# sharp_esp32s2_v1.net
KiCad netlist of a schematic drawn in EAGLE
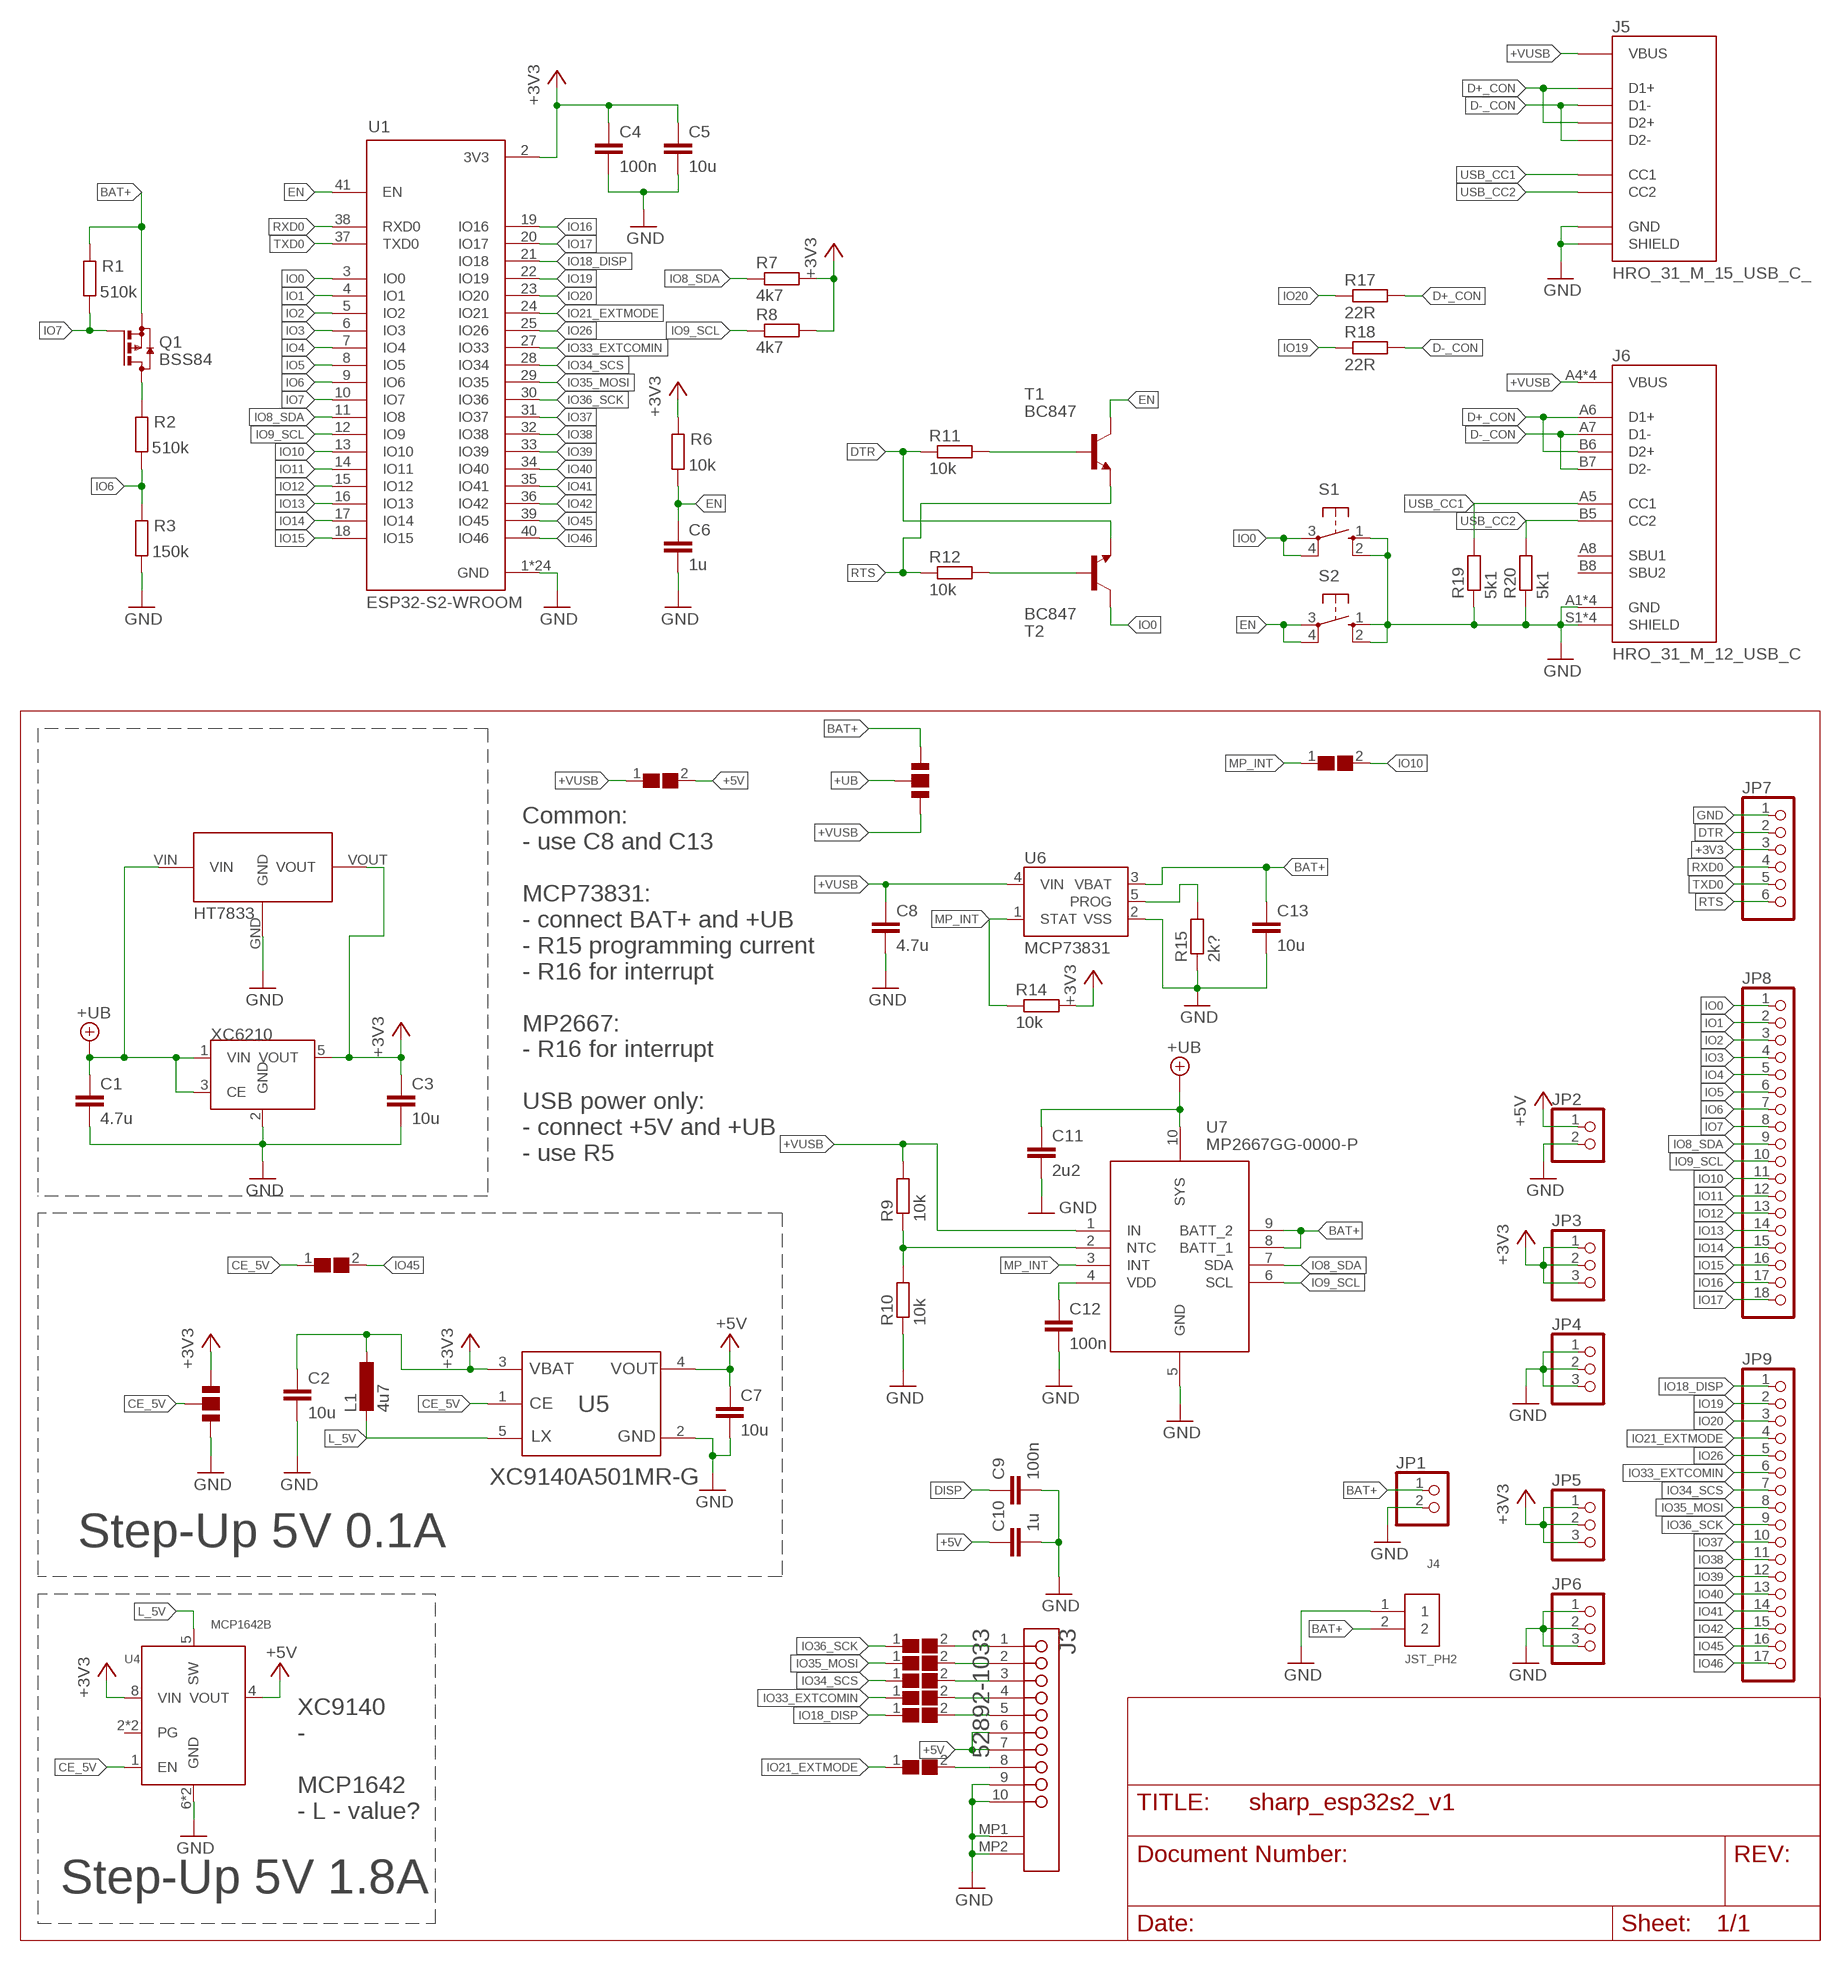
[diagram p0: schematic, sheet 1]

(export (version "E")
  (design (tool "Eeschema 10.0.6"))
  (components
    (comp (ref "C1")
      (value "4.7u")
      (footprint "eagle-import:C1206")
      (libsource (lib "eagle-import") (part "C-EUC1206"))
    )
    (comp (ref "C2")
      (value "10u")
      (footprint "eagle-import:C0603K")
      (libsource (lib "eagle-import") (part "C-EUC0603K"))
    )
    (comp (ref "C3")
      (value "10u")
      (footprint "eagle-import:C1206")
      (libsource (lib "eagle-import") (part "C-EUC1206"))
    )
    (comp (ref "C4")
      (value "100n")
      (footprint "eagle-import:C0603K")
      (libsource (lib "eagle-import") (part "C-EUC0603K"))
    )
    (comp (ref "C5")
      (value "10u")
      (footprint "eagle-import:C1206")
      (libsource (lib "eagle-import") (part "C-EUC1206"))
    )
    (comp (ref "C6")
      (value "1u")
      (footprint "eagle-import:C0603K")
      (libsource (lib "eagle-import") (part "C-EUC0603K"))
    )
    (comp (ref "C7")
      (value "10u")
      (footprint "eagle-import:C0603K")
      (libsource (lib "eagle-import") (part "C-EUC0603K"))
    )
    (comp (ref "C8")
      (value "4.7u")
      (footprint "eagle-import:C1206")
      (libsource (lib "eagle-import") (part "C-EUC1206"))
    )
    (comp (ref "C9")
      (value "100n")
      (footprint "eagle-import:C0603K")
      (libsource (lib "eagle-import") (part "C-EUC0603K"))
    )
    (comp (ref "C10")
      (value "1u")
      (footprint "eagle-import:C0603K")
      (libsource (lib "eagle-import") (part "C-EUC0603K"))
    )
    (comp (ref "C11")
      (value "2u2")
      (footprint "eagle-import:C1206")
      (libsource (lib "eagle-import") (part "C-EUC1206"))
    )
    (comp (ref "C12")
      (value "100n")
      (footprint "eagle-import:C0603K")
      (libsource (lib "eagle-import") (part "C-EUC0603K"))
    )
    (comp (ref "C13")
      (value "10u")
      (footprint "eagle-import:C1206")
      (libsource (lib "eagle-import") (part "C-EUC1206"))
    )
    (comp (ref "J1")
      (value "JUMPER")
      (footprint "eagle-import:2-WAY")
      (libsource (lib "eagle-import") (part "JUMPER"))
    )
    (comp (ref "J2")
      (value "JUMPER")
      (footprint "eagle-import:2-WAY")
      (libsource (lib "eagle-import") (part "JUMPER"))
    )
    (comp (ref "J3")
      (value "MOLEX_52892-1033MOLEX_52892-1033_0_0")
      (footprint "eagle-import:MOLEX_52892-1033_0")
      (fields (field (name "MF") "Molex") (field (name "MPN") "52892-1033"))
      (libsource (lib "eagle-import") (part "MOLEX_52892-1033MOLEX_52892-1033_0_0"))
    )
    (comp (ref "J4")
      (value "JST_PH2")
      (footprint "eagle-import:JSTPH2")
      (libsource (lib "eagle-import") (part "JST_PH2"))
    )
    (comp (ref "J5")
      (value "HRO_31_M_15_USB_C_")
      (footprint "eagle-import:HRO_31_M_15_USB_C")
      (libsource (lib "eagle-import") (part "HRO_31_M_15_USB_C_"))
    )
    (comp (ref "J6")
      (value "HRO_31_M_12_USB_C")
      (footprint "eagle-import:HRO_31_M_12_USB_C")
      (libsource (lib "eagle-import") (part "HRO_31_M_12_USB_C"))
    )
    (comp (ref "JP1")
      (value "PINHD-1X2")
      (footprint "eagle-import:1X02")
      (libsource (lib "eagle-import") (part "PINHD-1X2"))
    )
    (comp (ref "JP2")
      (value "PINHD-1X2")
      (footprint "eagle-import:1X02")
      (libsource (lib "eagle-import") (part "PINHD-1X2"))
    )
    (comp (ref "JP3")
      (value "PINHD-1X3")
      (footprint "eagle-import:1X03")
      (libsource (lib "eagle-import") (part "PINHD-1X3"))
    )
    (comp (ref "JP4")
      (value "PINHD-1X3")
      (footprint "eagle-import:1X03")
      (libsource (lib "eagle-import") (part "PINHD-1X3"))
    )
    (comp (ref "JP5")
      (value "PINHD-1X3")
      (footprint "eagle-import:1X03")
      (libsource (lib "eagle-import") (part "PINHD-1X3"))
    )
    (comp (ref "JP6")
      (value "PINHD-1X3")
      (footprint "eagle-import:1X03")
      (libsource (lib "eagle-import") (part "PINHD-1X3"))
    )
    (comp (ref "JP7")
      (value "PINHD-1X6")
      (footprint "eagle-import:1X06")
      (libsource (lib "eagle-import") (part "PINHD-1X6"))
    )
    (comp (ref "JP8")
      (value "PINHD-1X18")
      (footprint "eagle-import:1X18")
      (libsource (lib "eagle-import") (part "PINHD-1X18"))
    )
    (comp (ref "JP9")
      (value "PINHD-1X17")
      (footprint "eagle-import:1X17")
      (libsource (lib "eagle-import") (part "PINHD-1X17"))
    )
    (comp (ref "L1")
      (value "4u7")
      (footprint "eagle-import:L3225M")
      (libsource (lib "eagle-import") (part "L-EUL3225M"))
    )
    (comp (ref "Q1")
      (value "BSS84")
      (footprint "eagle-import:SOT23")
      (libsource (lib "eagle-import") (part "BSS84"))
    )
    (comp (ref "R1")
      (value "510k")
      (footprint "eagle-import:R0603")
      (libsource (lib "eagle-import") (part "R-EU_R0603"))
    )
    (comp (ref "R2")
      (value "510k")
      (footprint "eagle-import:R0603")
      (libsource (lib "eagle-import") (part "R-EU_R0603"))
    )
    (comp (ref "R3")
      (value "150k")
      (footprint "eagle-import:R0603")
      (libsource (lib "eagle-import") (part "R-EU_R0603"))
    )
    (comp (ref "R6")
      (value "10k")
      (footprint "eagle-import:R0603")
      (libsource (lib "eagle-import") (part "R-EU_R0603"))
    )
    (comp (ref "R7")
      (value "4k7")
      (footprint "eagle-import:R0603")
      (libsource (lib "eagle-import") (part "R-EU_R0603"))
    )
    (comp (ref "R8")
      (value "4k7")
      (footprint "eagle-import:R0603")
      (libsource (lib "eagle-import") (part "R-EU_R0603"))
    )
    (comp (ref "R9")
      (value "10k")
      (footprint "eagle-import:R0603")
      (libsource (lib "eagle-import") (part "R-EU_R0603"))
    )
    (comp (ref "R10")
      (value "10k")
      (footprint "eagle-import:R0603")
      (libsource (lib "eagle-import") (part "R-EU_R0603"))
    )
    (comp (ref "R11")
      (value "10k")
      (footprint "eagle-import:R0603")
      (libsource (lib "eagle-import") (part "R-EU_R0603"))
    )
    (comp (ref "R12")
      (value "10k")
      (footprint "eagle-import:R0603")
      (libsource (lib "eagle-import") (part "R-EU_R0603"))
    )
    (comp (ref "R14")
      (value "10k")
      (footprint "eagle-import:R0603")
      (libsource (lib "eagle-import") (part "R-EU_R0603"))
    )
    (comp (ref "R15")
      (value "2k?")
      (footprint "eagle-import:R0603")
      (libsource (lib "eagle-import") (part "R-EU_R0603"))
    )
    (comp (ref "R17")
      (value "22R")
      (footprint "eagle-import:R0603")
      (libsource (lib "eagle-import") (part "R-EU_R0603"))
    )
    (comp (ref "R18")
      (value "22R")
      (footprint "eagle-import:R0603")
      (libsource (lib "eagle-import") (part "R-EU_R0603"))
    )
    (comp (ref "R19")
      (value "5k1")
      (footprint "eagle-import:R0603")
      (libsource (lib "eagle-import") (part "R-EU_R0603"))
    )
    (comp (ref "R20")
      (value "5k1")
      (footprint "eagle-import:R0603")
      (libsource (lib "eagle-import") (part "R-EU_R0603"))
    )
    (comp (ref "S1")
      (value "10-XX")
      (footprint "eagle-import:B3F-10XX")
      (fields (field (name "MPN") "B3F-1000"))
      (libsource (lib "eagle-import") (part "10-XX"))
    )
    (comp (ref "S2")
      (value "10-XX")
      (footprint "eagle-import:B3F-10XX")
      (fields (field (name "MPN") "B3F-1000"))
      (libsource (lib "eagle-import") (part "10-XX"))
    )
    (comp (ref "T1")
      (value "BC847")
      (footprint "eagle-import:SOT23")
      (libsource (lib "eagle-import") (part "BC847"))
    )
    (comp (ref "T2")
      (value "BC847")
      (footprint "eagle-import:SOT23")
      (libsource (lib "eagle-import") (part "BC847"))
    )
    (comp (ref "U$1")
      (value "SOLDER_JUMPER")
      (footprint "eagle-import:SOLDER_JUMPER")
      (libsource (lib "eagle-import") (part "SOLDER_JUMPER"))
    )
    (comp (ref "U$2")
      (value "SOLDER_JUMPER")
      (footprint "eagle-import:SOLDER_JUMPER")
      (libsource (lib "eagle-import") (part "SOLDER_JUMPER"))
    )
    (comp (ref "U$3")
      (value "SOLDER_JUMPER")
      (footprint "eagle-import:SOLDER_JUMPER")
      (libsource (lib "eagle-import") (part "SOLDER_JUMPER"))
    )
    (comp (ref "U$4")
      (value "SOLDER_JUMPER")
      (footprint "eagle-import:SOLDER_JUMPER")
      (libsource (lib "eagle-import") (part "SOLDER_JUMPER"))
    )
    (comp (ref "U$5")
      (value "SOLDER_JUMPER")
      (footprint "eagle-import:SOLDER_JUMPER")
      (libsource (lib "eagle-import") (part "SOLDER_JUMPER"))
    )
    (comp (ref "U$6")
      (value "SOLDER_JUMPER")
      (footprint "eagle-import:SOLDER_JUMPER")
      (libsource (lib "eagle-import") (part "SOLDER_JUMPER"))
    )
    (comp (ref "U$7")
      (value "SOLDER_JUMPER")
      (footprint "eagle-import:SOLDER_JUMPER")
      (libsource (lib "eagle-import") (part "SOLDER_JUMPER"))
    )
    (comp (ref "U$8")
      (value "SOLDER_JUMPER")
      (footprint "eagle-import:SOLDER_JUMPER")
      (libsource (lib "eagle-import") (part "SOLDER_JUMPER"))
    )
    (comp (ref "U$9")
      (value "SOLDER_JUMPER")
      (footprint "eagle-import:SOLDER_JUMPER")
      (libsource (lib "eagle-import") (part "SOLDER_JUMPER"))
    )
    (comp (ref "U1")
      (value "ESP32-S2-WROOM")
      (footprint "eagle-import:XCVR_ESP32-S2-WROOM")
      (fields (field (name "MF") "Espressif Systems"))
      (libsource (lib "eagle-import") (part "ESP32-S2-WROOM"))
    )
    (comp (ref "U2")
      (value "HT7833")
      (footprint "eagle-import:SOT89")
      (libsource (lib "eagle-import") (part "HT7833"))
    )
    (comp (ref "U3")
      (value "XC6210")
      (footprint "eagle-import:SOT-23-5")
      (libsource (lib "eagle-import") (part "XC6210"))
    )
    (comp (ref "U4")
      (value "MCP1642B")
      (footprint "eagle-import:MSOP8")
      (libsource (lib "eagle-import") (part "MCP1642B"))
    )
    (comp (ref "U5")
      (value "TOREX_XC9140A501MR-GTOREX_XC9140A501MR-G_0_0")
      (footprint "eagle-import:TOREX_XC9140A501MR-G_0")
      (fields
        (field (name "DIGIKEY_PART_NUMBER") "893-1181-1-ND")
        (field (name "MF") "Torex")
        (field (name "MOUSER_PART_NUMBER") "865-XC9140A501MR-G")
      )
      (libsource (lib "eagle-import") (part "TOREX_XC9140A501MR-GTOREX_XC9140A501MR-G_0_0"))
    )
    (comp (ref "U6")
      (value "MCP73831")
      (footprint "eagle-import:SOT95P290X120-5")
      (libsource (lib "eagle-import") (part "MCP73831"))
    )
    (comp (ref "U7")
      (value "MP2667GG-0000-P")
      (footprint "eagle-import:QFN50P200X200X105-10N")
      (fields (field (name "MOUSER_PART_NUMBER") "946-MP2667GG-0000-P"))
      (libsource (lib "eagle-import") (part "MP2667GG-0000-P"))
    )
  )
  (nets
    (net (code "1") (name "+3V3") (class "Default")
      (node (ref "C2") (pin "1") (pinfunction "1_1") (pintype "passive"))
      (node (ref "C3") (pin "1") (pinfunction "1_1") (pintype "passive"))
      (node (ref "C4") (pin "1") (pinfunction "1_1") (pintype "passive"))
      (node (ref "C5") (pin "1") (pinfunction "1_1") (pintype "passive"))
      (node (ref "J1") (pin "P$3") (pinfunction "P$3_P$3") (pintype "bidirectional"))
      (node (ref "JP3") (pin "1") (pinfunction "1_1") (pintype "passive"))
      (node (ref "JP3") (pin "2") (pinfunction "2_2") (pintype "passive"))
      (node (ref "JP3") (pin "3") (pinfunction "3_3") (pintype "passive"))
      (node (ref "JP5") (pin "1") (pinfunction "1_1") (pintype "passive"))
      (node (ref "JP5") (pin "2") (pinfunction "2_2") (pintype "passive"))
      (node (ref "JP5") (pin "3") (pinfunction "3_3") (pintype "passive"))
      (node (ref "JP7") (pin "3") (pinfunction "3_3") (pintype "passive"))
      (node (ref "L1") (pin "1") (pinfunction "1_1") (pintype "passive"))
      (node (ref "R14") (pin "2") (pinfunction "2_2") (pintype "passive"))
      (node (ref "R6") (pin "2") (pinfunction "2_2") (pintype "passive"))
      (node (ref "R7") (pin "2") (pinfunction "2_2") (pintype "passive"))
      (node (ref "R8") (pin "2") (pinfunction "2_2") (pintype "passive"))
      (node (ref "U1") (pin "2") (pinfunction "3V3_2") (pintype "power_in"))
      (node (ref "U2") (pin "VOUT") (pinfunction "VOUT_VOUT") (pintype "bidirectional"))
      (node (ref "U3") (pin "5") (pinfunction "VOUT_5") (pintype "power_in"))
      (node (ref "U4") (pin "8") (pinfunction "VIN_8") (pintype "power_in"))
      (node (ref "U5") (pin "3") (pinfunction "VBAT_3") (pintype "input"))
    )
    (net (code "2") (name "+5V") (class "Default")
      (node (ref "C10") (pin "1") (pinfunction "1_1") (pintype "passive"))
      (node (ref "C7") (pin "1") (pinfunction "1_1") (pintype "passive"))
      (node (ref "J3") (pin "6") (pinfunction "6_6") (pintype "passive"))
      (node (ref "J3") (pin "7") (pinfunction "7_7") (pintype "passive"))
      (node (ref "JP2") (pin "1") (pinfunction "1_1") (pintype "passive"))
      (node (ref "U$7") (pin "2") (pinfunction "2_2") (pintype "bidirectional"))
      (node (ref "U4") (pin "4") (pinfunction "VOUT_4") (pintype "power_in"))
      (node (ref "U5") (pin "4") (pinfunction "VOUT_4") (pintype "output"))
    )
    (net (code "3") (name "+UB") (class "Default")
      (node (ref "C1") (pin "1") (pinfunction "1_1") (pintype "passive"))
      (node (ref "C11") (pin "1") (pinfunction "1_1") (pintype "passive"))
      (node (ref "J2") (pin "P$1") (pinfunction "P$1_P$1") (pintype "bidirectional"))
      (node (ref "U2") (pin "VIN") (pinfunction "VIN_VIN") (pintype "bidirectional"))
      (node (ref "U3") (pin "1") (pinfunction "VIN_1") (pintype "power_in"))
      (node (ref "U3") (pin "3") (pinfunction "CE_3") (pintype "power_in"))
      (node (ref "U7") (pin "10") (pinfunction "SYS_10") (pintype "bidirectional"))
    )
    (net (code "4") (name "+VUSB") (class "Default")
      (node (ref "C8") (pin "1") (pinfunction "1_1") (pintype "passive"))
      (node (ref "J2") (pin "P$2") (pinfunction "P$2_P$2") (pintype "bidirectional"))
      (node (ref "J5") (pin "P$13") (pinfunction "VBUS_P$13") (pintype "passive"))
      (node (ref "J5") (pin "P$2") (pinfunction "VBUS_P$2") (pintype "passive"))
      (node (ref "J5") (pin "P$6") (pinfunction "VBUS_P$6") (pintype "passive"))
      (node (ref "J5") (pin "P$9") (pinfunction "VBUS_P$9") (pintype "passive"))
      (node (ref "J6") (pin "A4") (pinfunction "VBUS_A4") (pintype "passive"))
      (node (ref "J6") (pin "A9") (pinfunction "VBUS_A9") (pintype "passive"))
      (node (ref "J6") (pin "B4") (pinfunction "VBUS_B4") (pintype "passive"))
      (node (ref "J6") (pin "B9") (pinfunction "VBUS_B9") (pintype "passive"))
      (node (ref "R9") (pin "2") (pinfunction "2_2") (pintype "passive"))
      (node (ref "U$7") (pin "1") (pinfunction "1_1") (pintype "bidirectional"))
      (node (ref "U6") (pin "4") (pinfunction "VIN_4") (pintype "power_in"))
      (node (ref "U7") (pin "1") (pinfunction "IN_1") (pintype "bidirectional"))
    )
    (net (code "5") (name "BAT+") (class "Default")
      (node (ref "C13") (pin "1") (pinfunction "1_1") (pintype "passive"))
      (node (ref "J2") (pin "P$3") (pinfunction "P$3_P$3") (pintype "bidirectional"))
      (node (ref "J4") (pin "2") (pinfunction "2_2") (pintype "bidirectional"))
      (node (ref "JP1") (pin "1") (pinfunction "1_1") (pintype "passive"))
      (node (ref "Q1") (pin "2") (pinfunction "S_2") (pintype "passive"))
      (node (ref "R1") (pin "2") (pinfunction "2_2") (pintype "passive"))
      (node (ref "U6") (pin "3") (pinfunction "VBAT_3") (pintype "power_in"))
      (node (ref "U7") (pin "8") (pinfunction "BATT_1_8") (pintype "bidirectional"))
      (node (ref "U7") (pin "9") (pinfunction "BATT_2_9") (pintype "bidirectional"))
    )
    (net (code "6") (name "CE_5V") (class "Default")
      (node (ref "J1") (pin "P$1") (pinfunction "P$1_P$1") (pintype "bidirectional"))
      (node (ref "U$9") (pin "1") (pinfunction "1_1") (pintype "bidirectional"))
      (node (ref "U4") (pin "1") (pinfunction "EN_1") (pintype "input"))
      (node (ref "U5") (pin "1") (pinfunction "CE_1") (pintype "passive"))
    )
    (net (code "7") (name "D+_CON") (class "Default")
      (node (ref "J5") (pin "P$11") (pinfunction "D2+_P$11") (pintype "passive"))
      (node (ref "J5") (pin "P$4") (pinfunction "D1+_P$4") (pintype "passive"))
      (node (ref "J6") (pin "A6") (pinfunction "D1+_A6") (pintype "passive"))
      (node (ref "J6") (pin "B6") (pinfunction "D2+_B6") (pintype "passive"))
      (node (ref "R17") (pin "2") (pinfunction "2_2") (pintype "passive"))
    )
    (net (code "8") (name "D-_CON") (class "Default")
      (node (ref "J5") (pin "P$10") (pinfunction "D2-_P$10") (pintype "passive"))
      (node (ref "J5") (pin "P$3") (pinfunction "D1-_P$3") (pintype "passive"))
      (node (ref "J6") (pin "A7") (pinfunction "D1-_A7") (pintype "passive"))
      (node (ref "J6") (pin "B7") (pinfunction "D2-_B7") (pintype "passive"))
      (node (ref "R18") (pin "2") (pinfunction "2_2") (pintype "passive"))
    )
    (net (code "9") (name "DISP") (class "Default")
      (node (ref "C9") (pin "1") (pinfunction "1_1") (pintype "passive"))
      (node (ref "J3") (pin "5") (pinfunction "5_5") (pintype "passive"))
      (node (ref "U$5") (pin "2") (pinfunction "2_2") (pintype "bidirectional"))
    )
    (net (code "10") (name "DTR") (class "Default")
      (node (ref "JP7") (pin "2") (pinfunction "2_2") (pintype "passive"))
      (node (ref "R11") (pin "1") (pinfunction "1_1") (pintype "passive"))
      (node (ref "T2") (pin "2") (pinfunction "E_2") (pintype "passive"))
    )
    (net (code "11") (name "EN") (class "Default")
      (node (ref "C6") (pin "1") (pinfunction "1_1") (pintype "passive"))
      (node (ref "R6") (pin "1") (pinfunction "1_1") (pintype "passive"))
      (node (ref "S2") (pin "3") (pinfunction "P_3") (pintype "passive"))
      (node (ref "S2") (pin "4") (pinfunction "P1_4") (pintype "passive"))
      (node (ref "T1") (pin "3") (pinfunction "C_3") (pintype "passive"))
      (node (ref "U1") (pin "41") (pinfunction "EN_41") (pintype "input"))
    )
    (net (code "12") (name "GND") (class "Default")
      (node (ref "C1") (pin "2") (pinfunction "2_2") (pintype "passive"))
      (node (ref "C10") (pin "2") (pinfunction "2_2") (pintype "passive"))
      (node (ref "C11") (pin "2") (pinfunction "2_2") (pintype "passive"))
      (node (ref "C12") (pin "2") (pinfunction "2_2") (pintype "passive"))
      (node (ref "C13") (pin "2") (pinfunction "2_2") (pintype "passive"))
      (node (ref "C2") (pin "2") (pinfunction "2_2") (pintype "passive"))
      (node (ref "C3") (pin "2") (pinfunction "2_2") (pintype "passive"))
      (node (ref "C4") (pin "2") (pinfunction "2_2") (pintype "passive"))
      (node (ref "C5") (pin "2") (pinfunction "2_2") (pintype "passive"))
      (node (ref "C6") (pin "2") (pinfunction "2_2") (pintype "passive"))
      (node (ref "C7") (pin "2") (pinfunction "2_2") (pintype "passive"))
      (node (ref "C8") (pin "2") (pinfunction "2_2") (pintype "passive"))
      (node (ref "C9") (pin "2") (pinfunction "2_2") (pintype "passive"))
      (node (ref "J1") (pin "P$2") (pinfunction "P$2_P$2") (pintype "bidirectional"))
      (node (ref "J3") (pin "10") (pinfunction "10_10") (pintype "passive"))
      (node (ref "J3") (pin "9") (pinfunction "9_9") (pintype "passive"))
      (node (ref "J3") (pin "MP1") (pinfunction "MP1_MP1") (pintype "passive"))
      (node (ref "J3") (pin "MP2") (pinfunction "MP2_MP2") (pintype "passive"))
      (node (ref "J4") (pin "1") (pinfunction "1_1") (pintype "bidirectional"))
      (node (ref "J5") (pin "P$1") (pinfunction "GND_P$1") (pintype "passive"))
      (node (ref "J5") (pin "P$14") (pinfunction "GND_P$14") (pintype "passive"))
      (node (ref "J5") (pin "P$15") (pinfunction "SHIELD_P$15") (pintype "passive"))
      (node (ref "J5") (pin "P$16") (pinfunction "SHIELD_P$16") (pintype "passive"))
      (node (ref "J5") (pin "P$17") (pinfunction "SHIELD_P$17") (pintype "passive"))
      (node (ref "J5") (pin "P$18") (pinfunction "SHIELD_P$18") (pintype "passive"))
      (node (ref "J5") (pin "P$7") (pinfunction "GND_P$7") (pintype "passive"))
      (node (ref "J5") (pin "P$8") (pinfunction "GND_P$8") (pintype "passive"))
      (node (ref "J6") (pin "A1") (pinfunction "GND_A1") (pintype "passive"))
      (node (ref "J6") (pin "A12") (pinfunction "GND_A12") (pintype "passive"))
      (node (ref "J6") (pin "B1") (pinfunction "GND_B1") (pintype "passive"))
      (node (ref "J6") (pin "B12") (pinfunction "GND_B12") (pintype "passive"))
      (node (ref "J6") (pin "S1") (pinfunction "SHIELD_S1") (pintype "passive"))
      (node (ref "J6") (pin "S2") (pinfunction "SHIELD_S2") (pintype "passive"))
      (node (ref "J6") (pin "S3") (pinfunction "SHIELD_S3") (pintype "passive"))
      (node (ref "J6") (pin "S4") (pinfunction "SHIELD_S4") (pintype "passive"))
      (node (ref "JP1") (pin "2") (pinfunction "2_2") (pintype "passive"))
      (node (ref "JP2") (pin "2") (pinfunction "2_2") (pintype "passive"))
      (node (ref "JP4") (pin "1") (pinfunction "1_1") (pintype "passive"))
      (node (ref "JP4") (pin "2") (pinfunction "2_2") (pintype "passive"))
      (node (ref "JP4") (pin "3") (pinfunction "3_3") (pintype "passive"))
      (node (ref "JP6") (pin "1") (pinfunction "1_1") (pintype "passive"))
      (node (ref "JP6") (pin "2") (pinfunction "2_2") (pintype "passive"))
      (node (ref "JP6") (pin "3") (pinfunction "3_3") (pintype "passive"))
      (node (ref "JP7") (pin "1") (pinfunction "1_1") (pintype "passive"))
      (node (ref "R10") (pin "1") (pinfunction "1_1") (pintype "passive"))
      (node (ref "R15") (pin "1") (pinfunction "1_1") (pintype "passive"))
      (node (ref "R19") (pin "1") (pinfunction "1_1") (pintype "passive"))
      (node (ref "R20") (pin "1") (pinfunction "1_1") (pintype "passive"))
      (node (ref "R3") (pin "1") (pinfunction "1_1") (pintype "passive"))
      (node (ref "S1") (pin "1") (pinfunction "S_1") (pintype "passive"))
      (node (ref "S1") (pin "2") (pinfunction "S1_2") (pintype "passive"))
      (node (ref "S2") (pin "1") (pinfunction "S_1") (pintype "passive"))
      (node (ref "S2") (pin "2") (pinfunction "S1_2") (pintype "passive"))
      (node (ref "U1") (pin "1") (pinfunction "GND_1") (pintype "power_in"))
      (node (ref "U1") (pin "26") (pinfunction "GND_26") (pintype "power_in"))
      (node (ref "U1") (pin "42") (pinfunction "GND_42") (pintype "power_in"))
      (node (ref "U1") (pin "43.1") (pinfunction "GND_43.1") (pintype "power_in"))
      (node (ref "U1") (pin "43.10") (pinfunction "GND_43.10") (pintype "power_in"))
      (node (ref "U1") (pin "43.11") (pinfunction "GND_43.11") (pintype "power_in"))
      (node (ref "U1") (pin "43.12") (pinfunction "GND_43.12") (pintype "power_in"))
      (node (ref "U1") (pin "43.13") (pinfunction "GND_43.13") (pintype "power_in"))
      (node (ref "U1") (pin "43.14") (pinfunction "GND_43.14") (pintype "power_in"))
      (node (ref "U1") (pin "43.15") (pinfunction "GND_43.15") (pintype "power_in"))
      (node (ref "U1") (pin "43.16") (pinfunction "GND_43.16") (pintype "power_in"))
      (node (ref "U1") (pin "43.17") (pinfunction "GND_43.17") (pintype "power_in"))
      (node (ref "U1") (pin "43.18") (pinfunction "GND_43.18") (pintype "power_in"))
      (node (ref "U1") (pin "43.19") (pinfunction "GND_43.19") (pintype "power_in"))
      (node (ref "U1") (pin "43.2") (pinfunction "GND_43.2") (pintype "power_in"))
      (node (ref "U1") (pin "43.20") (pinfunction "GND_43.20") (pintype "power_in"))
      (node (ref "U1") (pin "43.21") (pinfunction "GND_43.21") (pintype "power_in"))
      (node (ref "U1") (pin "43.3") (pinfunction "GND_43.3") (pintype "power_in"))
      (node (ref "U1") (pin "43.4") (pinfunction "GND_43.4") (pintype "power_in"))
      (node (ref "U1") (pin "43.5") (pinfunction "GND_43.5") (pintype "power_in"))
      (node (ref "U1") (pin "43.6") (pinfunction "GND_43.6") (pintype "power_in"))
      (node (ref "U1") (pin "43.7") (pinfunction "GND_43.7") (pintype "power_in"))
      (node (ref "U1") (pin "43.8") (pinfunction "GND_43.8") (pintype "power_in"))
      (node (ref "U1") (pin "43.9") (pinfunction "GND_43.9") (pintype "power_in"))
      (node (ref "U2") (pin "GND") (pinfunction "GND_GND") (pintype "bidirectional"))
      (node (ref "U3") (pin "2") (pinfunction "GND_2") (pintype "power_in"))
      (node (ref "U4") (pin "6") (pinfunction "GND_6") (pintype "power_in"))
      (node (ref "U4") (pin "7") (pinfunction "GND_7") (pintype "power_in"))
      (node (ref "U5") (pin "2") (pinfunction "GND_2") (pintype "power_in"))
      (node (ref "U6") (pin "2") (pinfunction "VSS_2") (pintype "power_in"))
      (node (ref "U7") (pin "5") (pinfunction "GND_5") (pintype "bidirectional"))
    )
    (net (code "13") (name "IO0") (class "Default")
      (node (ref "JP8") (pin "1") (pinfunction "1_1") (pintype "passive"))
      (node (ref "S1") (pin "3") (pinfunction "P_3") (pintype "passive"))
      (node (ref "S1") (pin "4") (pinfunction "P1_4") (pintype "passive"))
      (node (ref "T2") (pin "3") (pinfunction "C_3") (pintype "passive"))
      (node (ref "U1") (pin "3") (pinfunction "IO0_3") (pintype "bidirectional"))
    )
    (net (code "14") (name "IO1") (class "Default")
      (node (ref "JP8") (pin "2") (pinfunction "2_2") (pintype "passive"))
      (node (ref "U1") (pin "4") (pinfunction "IO1_4") (pintype "bidirectional"))
    )
    (net (code "15") (name "IO2") (class "Default")
      (node (ref "JP8") (pin "3") (pinfunction "3_3") (pintype "passive"))
      (node (ref "U1") (pin "5") (pinfunction "IO2_5") (pintype "bidirectional"))
    )
    (net (code "16") (name "IO3") (class "Default")
      (node (ref "JP8") (pin "4") (pinfunction "4_4") (pintype "passive"))
      (node (ref "U1") (pin "6") (pinfunction "IO3_6") (pintype "bidirectional"))
    )
    (net (code "17") (name "IO4") (class "Default")
      (node (ref "JP8") (pin "5") (pinfunction "5_5") (pintype "passive"))
      (node (ref "U1") (pin "7") (pinfunction "IO4_7") (pintype "bidirectional"))
    )
    (net (code "18") (name "IO5") (class "Default")
      (node (ref "JP8") (pin "6") (pinfunction "6_6") (pintype "passive"))
      (node (ref "U1") (pin "8") (pinfunction "IO5_8") (pintype "bidirectional"))
    )
    (net (code "19") (name "IO6") (class "Default")
      (node (ref "JP8") (pin "7") (pinfunction "7_7") (pintype "passive"))
      (node (ref "R2") (pin "1") (pinfunction "1_1") (pintype "passive"))
      (node (ref "R3") (pin "2") (pinfunction "2_2") (pintype "passive"))
      (node (ref "U1") (pin "9") (pinfunction "IO6_9") (pintype "bidirectional"))
    )
    (net (code "20") (name "IO7") (class "Default")
      (node (ref "JP8") (pin "8") (pinfunction "8_8") (pintype "passive"))
      (node (ref "Q1") (pin "1") (pinfunction "G_1") (pintype "passive"))
      (node (ref "R1") (pin "1") (pinfunction "1_1") (pintype "passive"))
      (node (ref "U1") (pin "10") (pinfunction "IO7_10") (pintype "bidirectional"))
    )
    (net (code "21") (name "IO8_SDA") (class "Default")
      (node (ref "JP8") (pin "9") (pinfunction "9_9") (pintype "passive"))
      (node (ref "R7") (pin "1") (pinfunction "1_1") (pintype "passive"))
      (node (ref "U1") (pin "11") (pinfunction "IO8_11") (pintype "bidirectional"))
      (node (ref "U7") (pin "7") (pinfunction "SDA_7") (pintype "bidirectional"))
    )
    (net (code "22") (name "IO9_SCL") (class "Default")
      (node (ref "JP8") (pin "10") (pinfunction "10_10") (pintype "passive"))
      (node (ref "R8") (pin "1") (pinfunction "1_1") (pintype "passive"))
      (node (ref "U1") (pin "12") (pinfunction "IO9_12") (pintype "bidirectional"))
      (node (ref "U7") (pin "6") (pinfunction "SCL_6") (pintype "bidirectional"))
    )
    (net (code "23") (name "IO10") (class "Default")
      (node (ref "JP8") (pin "11") (pinfunction "11_11") (pintype "passive"))
      (node (ref "U$8") (pin "2") (pinfunction "2_2") (pintype "bidirectional"))
      (node (ref "U1") (pin "13") (pinfunction "IO10_13") (pintype "bidirectional"))
    )
    (net (code "24") (name "IO11") (class "Default")
      (node (ref "JP8") (pin "12") (pinfunction "12_12") (pintype "passive"))
      (node (ref "U1") (pin "14") (pinfunction "IO11_14") (pintype "bidirectional"))
    )
    (net (code "25") (name "IO12") (class "Default")
      (node (ref "JP8") (pin "13") (pinfunction "13_13") (pintype "passive"))
      (node (ref "U1") (pin "15") (pinfunction "IO12_15") (pintype "bidirectional"))
    )
    (net (code "26") (name "IO13") (class "Default")
      (node (ref "JP8") (pin "14") (pinfunction "14_14") (pintype "passive"))
      (node (ref "U1") (pin "16") (pinfunction "IO13_16") (pintype "bidirectional"))
    )
    (net (code "27") (name "IO14") (class "Default")
      (node (ref "JP8") (pin "15") (pinfunction "15_15") (pintype "passive"))
      (node (ref "U1") (pin "17") (pinfunction "IO14_17") (pintype "bidirectional"))
    )
    (net (code "28") (name "IO15") (class "Default")
      (node (ref "JP8") (pin "16") (pinfunction "16_16") (pintype "passive"))
      (node (ref "U1") (pin "18") (pinfunction "IO15_18") (pintype "bidirectional"))
    )
    (net (code "29") (name "IO16") (class "Default")
      (node (ref "JP8") (pin "17") (pinfunction "17_17") (pintype "passive"))
      (node (ref "U1") (pin "19") (pinfunction "IO16_19") (pintype "bidirectional"))
    )
    (net (code "30") (name "IO17") (class "Default")
      (node (ref "JP8") (pin "18") (pinfunction "18_18") (pintype "passive"))
      (node (ref "U1") (pin "20") (pinfunction "IO17_20") (pintype "bidirectional"))
    )
    (net (code "31") (name "IO18_DISP") (class "Default")
      (node (ref "JP9") (pin "1") (pinfunction "1_1") (pintype "passive"))
      (node (ref "U$5") (pin "1") (pinfunction "1_1") (pintype "bidirectional"))
      (node (ref "U1") (pin "21") (pinfunction "IO18_21") (pintype "bidirectional"))
    )
    (net (code "32") (name "IO19") (class "Default")
      (node (ref "JP9") (pin "2") (pinfunction "2_2") (pintype "passive"))
      (node (ref "R18") (pin "1") (pinfunction "1_1") (pintype "passive"))
      (node (ref "U1") (pin "22") (pinfunction "IO19_22") (pintype "bidirectional"))
    )
    (net (code "33") (name "IO20") (class "Default")
      (node (ref "JP9") (pin "3") (pinfunction "3_3") (pintype "passive"))
      (node (ref "R17") (pin "1") (pinfunction "1_1") (pintype "passive"))
      (node (ref "U1") (pin "23") (pinfunction "IO20_23") (pintype "bidirectional"))
    )
    (net (code "34") (name "IO21_EXTMODE") (class "Default")
      (node (ref "JP9") (pin "4") (pinfunction "4_4") (pintype "passive"))
      (node (ref "U$6") (pin "1") (pinfunction "1_1") (pintype "bidirectional"))
      (node (ref "U1") (pin "24") (pinfunction "IO21_24") (pintype "bidirectional"))
    )
    (net (code "35") (name "IO26") (class "Default")
      (node (ref "JP9") (pin "5") (pinfunction "5_5") (pintype "passive"))
      (node (ref "U1") (pin "25") (pinfunction "IO26_25") (pintype "bidirectional"))
    )
    (net (code "36") (name "IO33_EXTCOMIN") (class "Default")
      (node (ref "JP9") (pin "6") (pinfunction "6_6") (pintype "passive"))
      (node (ref "U$4") (pin "1") (pinfunction "1_1") (pintype "bidirectional"))
      (node (ref "U1") (pin "27") (pinfunction "IO33_27") (pintype "bidirectional"))
    )
    (net (code "37") (name "IO34_SCS") (class "Default")
      (node (ref "JP9") (pin "7") (pinfunction "7_7") (pintype "passive"))
      (node (ref "U$3") (pin "1") (pinfunction "1_1") (pintype "bidirectional"))
      (node (ref "U1") (pin "28") (pinfunction "IO34_28") (pintype "bidirectional"))
    )
    (net (code "38") (name "IO35_MOSI") (class "Default")
      (node (ref "JP9") (pin "8") (pinfunction "8_8") (pintype "passive"))
      (node (ref "U$2") (pin "1") (pinfunction "1_1") (pintype "bidirectional"))
      (node (ref "U1") (pin "29") (pinfunction "IO35_29") (pintype "bidirectional"))
    )
    (net (code "39") (name "IO36_SCK") (class "Default")
      (node (ref "JP9") (pin "9") (pinfunction "9_9") (pintype "passive"))
      (node (ref "U$1") (pin "1") (pinfunction "1_1") (pintype "bidirectional"))
      (node (ref "U1") (pin "30") (pinfunction "IO36_30") (pintype "bidirectional"))
    )
    (net (code "40") (name "IO37") (class "Default")
      (node (ref "JP9") (pin "10") (pinfunction "10_10") (pintype "passive"))
      (node (ref "U1") (pin "31") (pinfunction "IO37_31") (pintype "bidirectional"))
    )
    (net (code "41") (name "IO38") (class "Default")
      (node (ref "JP9") (pin "11") (pinfunction "11_11") (pintype "passive"))
      (node (ref "U1") (pin "32") (pinfunction "IO38_32") (pintype "bidirectional"))
    )
    (net (code "42") (name "IO39") (class "Default")
      (node (ref "JP9") (pin "12") (pinfunction "12_12") (pintype "passive"))
      (node (ref "U1") (pin "33") (pinfunction "IO39_33") (pintype "bidirectional"))
    )
    (net (code "43") (name "IO40") (class "Default")
      (node (ref "JP9") (pin "13") (pinfunction "13_13") (pintype "passive"))
      (node (ref "U1") (pin "34") (pinfunction "IO40_34") (pintype "bidirectional"))
    )
    (net (code "44") (name "IO41") (class "Default")
      (node (ref "JP9") (pin "14") (pinfunction "14_14") (pintype "passive"))
      (node (ref "U1") (pin "35") (pinfunction "IO41_35") (pintype "bidirectional"))
    )
    (net (code "45") (name "IO42") (class "Default")
      (node (ref "JP9") (pin "15") (pinfunction "15_15") (pintype "passive"))
      (node (ref "U1") (pin "36") (pinfunction "IO42_36") (pintype "bidirectional"))
    )
    (net (code "46") (name "IO45") (class "Default")
      (node (ref "JP9") (pin "16") (pinfunction "16_16") (pintype "passive"))
      (node (ref "U$9") (pin "2") (pinfunction "2_2") (pintype "bidirectional"))
      (node (ref "U1") (pin "39") (pinfunction "IO45_39") (pintype "bidirectional"))
    )
    (net (code "47") (name "IO46") (class "Default")
      (node (ref "JP9") (pin "17") (pinfunction "17_17") (pintype "passive"))
      (node (ref "U1") (pin "40") (pinfunction "IO46_40") (pintype "bidirectional"))
    )
    (net (code "48") (name "L_5V") (class "Default")
      (node (ref "L1") (pin "2") (pinfunction "2_2") (pintype "passive"))
      (node (ref "U4") (pin "5") (pinfunction "SW_5") (pintype "power_in"))
      (node (ref "U5") (pin "5") (pinfunction "LX_5") (pintype "passive"))
    )
    (net (code "49") (name "MP_INT") (class "Default")
      (node (ref "R14") (pin "1") (pinfunction "1_1") (pintype "passive"))
      (node (ref "U$8") (pin "1") (pinfunction "1_1") (pintype "bidirectional"))
      (node (ref "U6") (pin "1") (pinfunction "STAT_1") (pintype "output"))
      (node (ref "U7") (pin "3") (pinfunction "INT_3") (pintype "bidirectional"))
    )
    (net (code "50") (name "Net-(J3-Pad1)") (class "Default")
      (node (ref "J3") (pin "1") (pinfunction "1_1") (pintype "passive"))
      (node (ref "U$1") (pin "2") (pinfunction "2_2") (pintype "bidirectional"))
    )
    (net (code "51") (name "Net-(J3-Pad2)") (class "Default")
      (node (ref "J3") (pin "2") (pinfunction "2_2") (pintype "passive"))
      (node (ref "U$2") (pin "2") (pinfunction "2_2") (pintype "bidirectional"))
    )
    (net (code "52") (name "Net-(J3-Pad3)") (class "Default")
      (node (ref "J3") (pin "3") (pinfunction "3_3") (pintype "passive"))
      (node (ref "U$3") (pin "2") (pinfunction "2_2") (pintype "bidirectional"))
    )
    (net (code "53") (name "Net-(J3-Pad4)") (class "Default")
      (node (ref "J3") (pin "4") (pinfunction "4_4") (pintype "passive"))
      (node (ref "U$4") (pin "2") (pinfunction "2_2") (pintype "bidirectional"))
    )
    (net (code "54") (name "Net-(J3-Pad8)") (class "Default")
      (node (ref "J3") (pin "8") (pinfunction "8_8") (pintype "passive"))
      (node (ref "U$6") (pin "2") (pinfunction "2_2") (pintype "bidirectional"))
    )
    (net (code "55") (name "Net-(Q1-D)") (class "Default")
      (node (ref "Q1") (pin "3") (pinfunction "D_3") (pintype "passive"))
      (node (ref "R2") (pin "2") (pinfunction "2_2") (pintype "passive"))
    )
    (net (code "56") (name "Net-(T1-B)") (class "Default")
      (node (ref "R11") (pin "2") (pinfunction "2_2") (pintype "passive"))
      (node (ref "T1") (pin "1") (pinfunction "B_1") (pintype "passive"))
    )
    (net (code "57") (name "Net-(T2-B)") (class "Default")
      (node (ref "R12") (pin "2") (pinfunction "2_2") (pintype "passive"))
      (node (ref "T2") (pin "1") (pinfunction "B_1") (pintype "passive"))
    )
    (net (code "58") (name "Net-(U6-PROG)") (class "Default")
      (node (ref "R15") (pin "2") (pinfunction "2_2") (pintype "passive"))
      (node (ref "U6") (pin "5") (pinfunction "PROG_5") (pintype "input"))
    )
    (net (code "59") (name "Net-(U7-NTC)") (class "Default")
      (node (ref "R10") (pin "2") (pinfunction "2_2") (pintype "passive"))
      (node (ref "R9") (pin "1") (pinfunction "1_1") (pintype "passive"))
      (node (ref "U7") (pin "2") (pinfunction "NTC_2") (pintype "bidirectional"))
    )
    (net (code "60") (name "Net-(U7-VDD)") (class "Default")
      (node (ref "C12") (pin "1") (pinfunction "1_1") (pintype "passive"))
      (node (ref "U7") (pin "4") (pinfunction "VDD_4") (pintype "bidirectional"))
    )
    (net (code "61") (name "RTS") (class "Default")
      (node (ref "JP7") (pin "6") (pinfunction "6_6") (pintype "passive"))
      (node (ref "R12") (pin "1") (pinfunction "1_1") (pintype "passive"))
      (node (ref "T1") (pin "2") (pinfunction "E_2") (pintype "passive"))
    )
    (net (code "62") (name "RXD0") (class "Default")
      (node (ref "JP7") (pin "4") (pinfunction "4_4") (pintype "passive"))
      (node (ref "U1") (pin "38") (pinfunction "RXD0_38") (pintype "bidirectional"))
    )
    (net (code "63") (name "TXD0") (class "Default")
      (node (ref "JP7") (pin "5") (pinfunction "5_5") (pintype "passive"))
      (node (ref "U1") (pin "37") (pinfunction "TXD0_37") (pintype "bidirectional"))
    )
    (net (code "64") (name "USB_CC1") (class "Default")
      (node (ref "J5") (pin "P$5") (pinfunction "CC1_P$5") (pintype "passive"))
      (node (ref "J6") (pin "A5") (pinfunction "CC1_A5") (pintype "passive"))
      (node (ref "R19") (pin "2") (pinfunction "2_2") (pintype "passive"))
    )
    (net (code "65") (name "USB_CC2") (class "Default")
      (node (ref "J5") (pin "P$12") (pinfunction "CC2_P$12") (pintype "passive"))
      (node (ref "J6") (pin "B5") (pinfunction "CC2_B5") (pintype "passive"))
      (node (ref "R20") (pin "2") (pinfunction "2_2") (pintype "passive"))
    )
    (net (code "66") (name "unconnected-(J6-SBU1-PadA8)") (class "Default")
      (node (ref "J6") (pin "A8") (pinfunction "SBU1_A8") (pintype "passive"))
    )
    (net (code "67") (name "unconnected-(J6-SBU2-PadB8)") (class "Default")
      (node (ref "J6") (pin "B8") (pinfunction "SBU2_B8") (pintype "passive"))
    )
    (net (code "68") (name "unconnected-(U4-PG-Pad2)") (class "Default")
      (node (ref "U4") (pin "2") (pinfunction "PG_2") (pintype "no_connect"))
    )
    (net (code "69") (name "unconnected-(U4-PG-Pad3)") (class "Default")
      (node (ref "U4") (pin "3") (pinfunction "PG_3") (pintype "no_connect"))
    )
  )
)
